# schematic_easyeda.net
KiCad netlist of a schematic drawn in EasyEDA
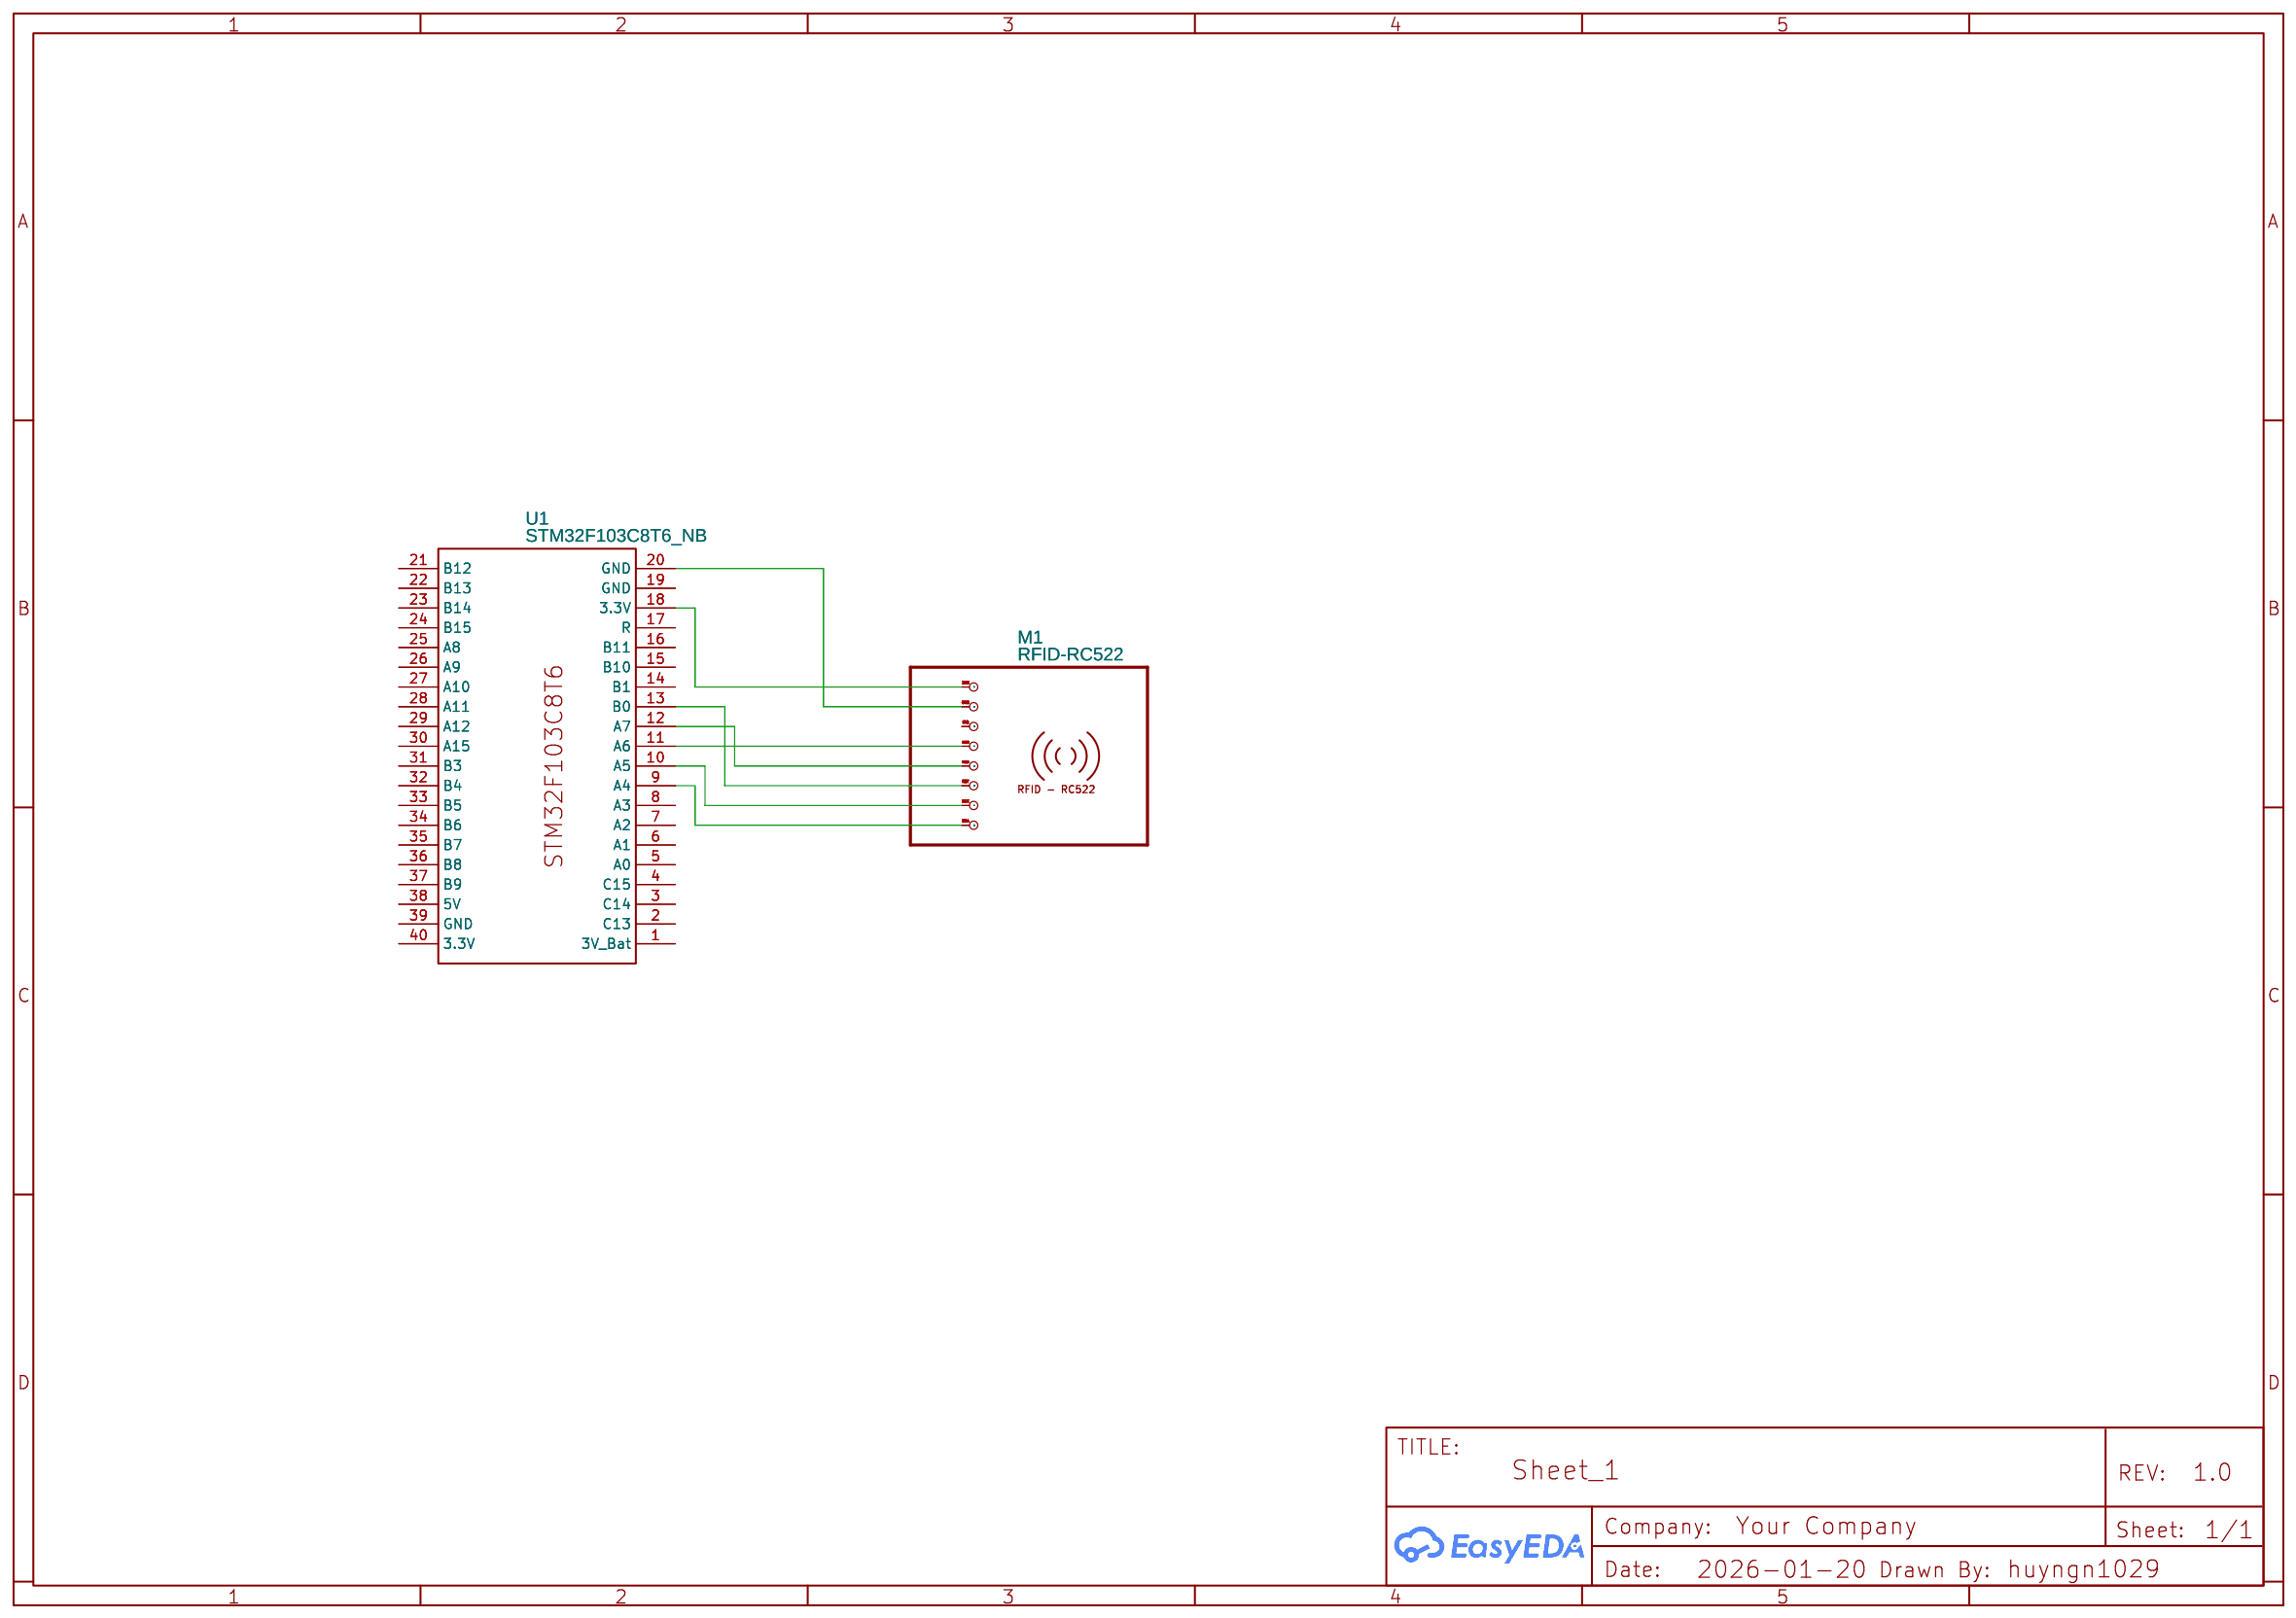
[diagram p0: schematic sheet]

(export (version "E")
  (design (tool "Eeschema 10.0.6"))
  (components
    (comp (ref "M1") (value "RFID-RC522") (libsource (lib "") (part "RFID-RC522")))
    (comp (ref "U1")
      (value "STM32F103C8T6_NB")
      (fields (field (name "Manufacturer Part") "STM32F103C8T6"))
      (libsource (lib "") (part "STM32F103C8T6_NB"))
    )
  )
  (nets
    (net (code "1") (name "Net-(M1-1)") (class "Default")
      (node (ref "M1") (pin "3V3") (pinfunction "1_3V3") (pintype "unspecified"))
      (node (ref "U1") (pin "18") (pinfunction "3.3V_18") (pintype "unspecified"))
    )
    (net (code "2") (name "Net-(M1-2)") (class "Default")
      (node (ref "M1") (pin "GND") (pinfunction "2_GND") (pintype "unspecified"))
      (node (ref "U1") (pin "20") (pinfunction "GND_20") (pintype "unspecified"))
    )
    (net (code "3") (name "Net-(M1-4)") (class "Default")
      (node (ref "M1") (pin "MISO") (pinfunction "4_MISO") (pintype "unspecified"))
      (node (ref "U1") (pin "11") (pinfunction "A6_11") (pintype "unspecified"))
    )
    (net (code "4") (name "Net-(M1-5)") (class "Default")
      (node (ref "M1") (pin "MOSI") (pinfunction "5_MOSI") (pintype "unspecified"))
      (node (ref "U1") (pin "12") (pinfunction "A7_12") (pintype "unspecified"))
    )
    (net (code "5") (name "Net-(M1-6)") (class "Default")
      (node (ref "M1") (pin "RST") (pinfunction "6_RST") (pintype "unspecified"))
      (node (ref "U1") (pin "13") (pinfunction "B0_13") (pintype "unspecified"))
    )
    (net (code "6") (name "Net-(M1-7)") (class "Default")
      (node (ref "M1") (pin "SCK") (pinfunction "7_SCK") (pintype "unspecified"))
      (node (ref "U1") (pin "10") (pinfunction "A5_10") (pintype "unspecified"))
    )
    (net (code "7") (name "Net-(M1-8)") (class "Default")
      (node (ref "M1") (pin "SDA") (pinfunction "8_SDA") (pintype "unspecified"))
      (node (ref "U1") (pin "9") (pinfunction "A4_9") (pintype "unspecified"))
    )
    (net (code "8") (name "unconnected-(M1-3-PadIRQ)") (class "Default")
      (node (ref "M1") (pin "IRQ") (pinfunction "3_IRQ") (pintype "unspecified"))
    )
    (net (code "9") (name "unconnected-(U1-3.3V-Pad40)") (class "Default")
      (node (ref "U1") (pin "40") (pinfunction "3.3V_40") (pintype "unspecified"))
    )
    (net (code "10") (name "unconnected-(U1-3V_Bat-Pad1)") (class "Default")
      (node (ref "U1") (pin "1") (pinfunction "3V_Bat_1") (pintype "unspecified"))
    )
    (net (code "11") (name "unconnected-(U1-5V-Pad38)") (class "Default")
      (node (ref "U1") (pin "38") (pinfunction "5V_38") (pintype "unspecified"))
    )
    (net (code "12") (name "unconnected-(U1-A0-Pad5)") (class "Default")
      (node (ref "U1") (pin "5") (pinfunction "A0_5") (pintype "unspecified"))
    )
    (net (code "13") (name "unconnected-(U1-A1-Pad6)") (class "Default")
      (node (ref "U1") (pin "6") (pinfunction "A1_6") (pintype "unspecified"))
    )
    (net (code "14") (name "unconnected-(U1-A2-Pad7)") (class "Default")
      (node (ref "U1") (pin "7") (pinfunction "A2_7") (pintype "unspecified"))
    )
    (net (code "15") (name "unconnected-(U1-A3-Pad8)") (class "Default")
      (node (ref "U1") (pin "8") (pinfunction "A3_8") (pintype "unspecified"))
    )
    (net (code "16") (name "unconnected-(U1-A8-Pad25)") (class "Default")
      (node (ref "U1") (pin "25") (pinfunction "A8_25") (pintype "unspecified"))
    )
    (net (code "17") (name "unconnected-(U1-A9-Pad26)") (class "Default")
      (node (ref "U1") (pin "26") (pinfunction "A9_26") (pintype "unspecified"))
    )
    (net (code "18") (name "unconnected-(U1-A10-Pad27)") (class "Default")
      (node (ref "U1") (pin "27") (pinfunction "A10_27") (pintype "unspecified"))
    )
    (net (code "19") (name "unconnected-(U1-A11-Pad28)") (class "Default")
      (node (ref "U1") (pin "28") (pinfunction "A11_28") (pintype "unspecified"))
    )
    (net (code "20") (name "unconnected-(U1-A12-Pad29)") (class "Default")
      (node (ref "U1") (pin "29") (pinfunction "A12_29") (pintype "unspecified"))
    )
    (net (code "21") (name "unconnected-(U1-A15-Pad30)") (class "Default")
      (node (ref "U1") (pin "30") (pinfunction "A15_30") (pintype "unspecified"))
    )
    (net (code "22") (name "unconnected-(U1-B1-Pad14)") (class "Default")
      (node (ref "U1") (pin "14") (pinfunction "B1_14") (pintype "unspecified"))
    )
    (net (code "23") (name "unconnected-(U1-B3-Pad31)") (class "Default")
      (node (ref "U1") (pin "31") (pinfunction "B3_31") (pintype "unspecified"))
    )
    (net (code "24") (name "unconnected-(U1-B4-Pad32)") (class "Default")
      (node (ref "U1") (pin "32") (pinfunction "B4_32") (pintype "unspecified"))
    )
    (net (code "25") (name "unconnected-(U1-B5-Pad33)") (class "Default")
      (node (ref "U1") (pin "33") (pinfunction "B5_33") (pintype "unspecified"))
    )
    (net (code "26") (name "unconnected-(U1-B6-Pad34)") (class "Default")
      (node (ref "U1") (pin "34") (pinfunction "B6_34") (pintype "unspecified"))
    )
    (net (code "27") (name "unconnected-(U1-B7-Pad35)") (class "Default")
      (node (ref "U1") (pin "35") (pinfunction "B7_35") (pintype "unspecified"))
    )
    (net (code "28") (name "unconnected-(U1-B8-Pad36)") (class "Default")
      (node (ref "U1") (pin "36") (pinfunction "B8_36") (pintype "unspecified"))
    )
    (net (code "29") (name "unconnected-(U1-B9-Pad37)") (class "Default")
      (node (ref "U1") (pin "37") (pinfunction "B9_37") (pintype "unspecified"))
    )
    (net (code "30") (name "unconnected-(U1-B10-Pad15)") (class "Default")
      (node (ref "U1") (pin "15") (pinfunction "B10_15") (pintype "unspecified"))
    )
    (net (code "31") (name "unconnected-(U1-B11-Pad16)") (class "Default")
      (node (ref "U1") (pin "16") (pinfunction "B11_16") (pintype "unspecified"))
    )
    (net (code "32") (name "unconnected-(U1-B12-Pad21)") (class "Default")
      (node (ref "U1") (pin "21") (pinfunction "B12_21") (pintype "bidirectional"))
    )
    (net (code "33") (name "unconnected-(U1-B13-Pad22)") (class "Default")
      (node (ref "U1") (pin "22") (pinfunction "B13_22") (pintype "bidirectional"))
    )
    (net (code "34") (name "unconnected-(U1-B14-Pad23)") (class "Default")
      (node (ref "U1") (pin "23") (pinfunction "B14_23") (pintype "bidirectional"))
    )
    (net (code "35") (name "unconnected-(U1-B15-Pad24)") (class "Default")
      (node (ref "U1") (pin "24") (pinfunction "B15_24") (pintype "bidirectional"))
    )
    (net (code "36") (name "unconnected-(U1-C13-Pad2)") (class "Default")
      (node (ref "U1") (pin "2") (pinfunction "C13_2") (pintype "unspecified"))
    )
    (net (code "37") (name "unconnected-(U1-C14-Pad3)") (class "Default")
      (node (ref "U1") (pin "3") (pinfunction "C14_3") (pintype "unspecified"))
    )
    (net (code "38") (name "unconnected-(U1-C15-Pad4)") (class "Default")
      (node (ref "U1") (pin "4") (pinfunction "C15_4") (pintype "unspecified"))
    )
    (net (code "39") (name "unconnected-(U1-GND-Pad19)") (class "Default")
      (node (ref "U1") (pin "19") (pinfunction "GND_19") (pintype "unspecified"))
    )
    (net (code "40") (name "unconnected-(U1-GND-Pad39)") (class "Default")
      (node (ref "U1") (pin "39") (pinfunction "GND_39") (pintype "unspecified"))
    )
    (net (code "41") (name "unconnected-(U1-R-Pad17)") (class "Default")
      (node (ref "U1") (pin "17") (pinfunction "R_17") (pintype "unspecified"))
    )
  )
)
